# MCU_Peripherals.net
KiCad netlist of a schematic drawn in Altium Designer
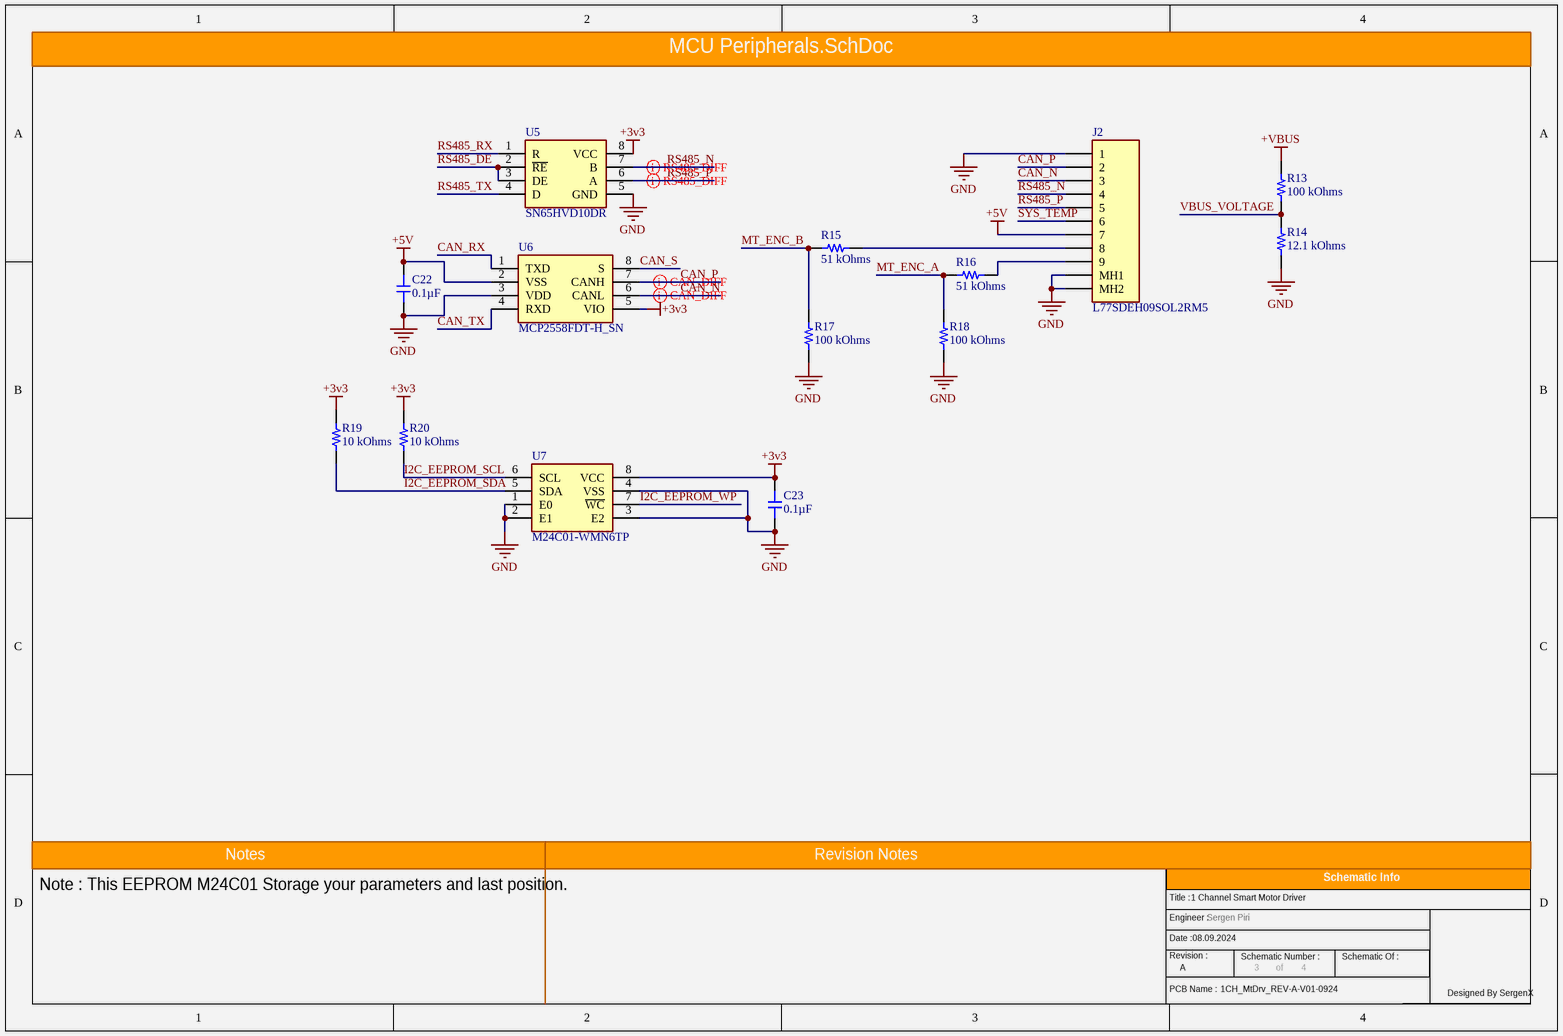
[diagram p0: MCU Peripherals.SchDoc]

(export (version "E")
  (design (tool "Eeschema 10.0.6"))
  (components
    (comp (ref "C22")
      (value "0.1µF")
      (footprint "0603_Footprint")
      (description "0.1uF 0603 Surface Capacitor")
      (libsource (lib "MainLibrary") (part "0.1uF 0603 Surface Capacitor"))
    )
    (comp (ref "C23")
      (value "0.1µF")
      (footprint "0603_Footprint")
      (description "0.1uF 0603 Surface Capacitor")
      (libsource (lib "MainLibrary") (part "0.1uF 0603 Surface Capacitor"))
    )
    (comp (ref "J2")
      (value "L77SDEH09SOL2RM5")
      (footprint "L77SDEH09SOL2RM5")
      (fields (field (name "MOUSER PART NUMBER") "523-L77SDEH09SOL2RM5"))
      (libsource (lib "MainLibrary") (part "L77SDEH09SOL2RM5"))
    )
    (comp (ref "R13")
      (value "100 kOhms")
      (footprint "0603_RES")
      (description "100k Ohm 0603")
      (libsource (lib "MainLibrary") (part "100k Ohm 0603"))
    )
    (comp (ref "R14")
      (value "12.1 kOhms")
      (footprint "0603_RES")
      (description "12.1 kOhms 0603")
      (libsource (lib "MainLibrary") (part "12.1 kOhms 0603"))
    )
    (comp (ref "R15")
      (value "51 kOhms")
      (footprint "0603_RES")
      (description "51k Ohm 0603")
      (libsource (lib "MainLibrary") (part "51k Ohm 0603"))
    )
    (comp (ref "R16")
      (value "51 kOhms")
      (footprint "0603_RES")
      (description "51k Ohm 0603")
      (libsource (lib "MainLibrary") (part "51k Ohm 0603"))
    )
    (comp (ref "R17")
      (value "100 kOhms")
      (footprint "0603_RES")
      (description "100k Ohm 0603")
      (libsource (lib "MainLibrary") (part "100k Ohm 0603"))
    )
    (comp (ref "R18")
      (value "100 kOhms")
      (footprint "0603_RES")
      (description "100k Ohm 0603")
      (libsource (lib "MainLibrary") (part "100k Ohm 0603"))
    )
    (comp (ref "R19")
      (value "10 kOhms")
      (footprint "0603_RES")
      (description "10 kOhms 0603")
      (libsource (lib "MainLibrary") (part "10 kOhms 0603"))
    )
    (comp (ref "R20")
      (value "10 kOhms")
      (footprint "0603_RES")
      (description "10 kOhms 0603")
      (libsource (lib "MainLibrary") (part "10 kOhms 0603"))
    )
    (comp (ref "U5")
      (value "SN65HVD10DR")
      (footprint "SOIC127P600X175-8N")
      (description "3.3V RS485 TRANSRECEIVER IC")
      (fields (field (name "MOUSER PART NUMBER") "595-SN65HVD10DR"))
      (libsource (lib "MainLibrary") (part "SN65HVD10DR"))
    )
    (comp (ref "U6")
      (value "MCP2558FDT-H_SN")
      (footprint "SOIC127P600X175-8N")
      (description "CAN Interface IC CAN FD Transceiver with Silent Mode")
      (fields
        (field (name "MANUFACTURER_PART_NUMBER") "MCP2558FDT-H/SN")
        (field (name "MOUSER PART NUMBER") "579-MCP2558FDT-H/SN")
      )
      (libsource (lib "MainLibrary") (part "MCP2558FDT-H_SN"))
    )
    (comp (ref "U7")
      (value "M24C01-WMN6TP")
      (footprint "MainLibrary:SOIC127P600X175-8N")
      (description "EEPROM Memory IC 1Kb (128 x 8) IÂ²C 400kHz 900ns 8-SO")
      (fields (field (name "MF") "STMicroelectronics"))
      (libsource (lib "MainLibrary") (part "M24C01-WMN6TP"))
    )
  )
  (nets
    (net (code "1") (name "+3v3") (class "Default")
      (node (ref "C23") (pin "1") (pinfunction "1_1") (pintype "passive"))
      (node (ref "R19") (pin "2") (pinfunction "2_2") (pintype "passive"))
      (node (ref "R20") (pin "2") (pinfunction "2_2") (pintype "passive"))
      (node (ref "U5") (pin "8") (pinfunction "VCC_8") (pintype "passive"))
      (node (ref "U6") (pin "5") (pinfunction "VIO_5") (pintype "passive"))
      (node (ref "U7") (pin "8") (pinfunction "VCC_8") (pintype "power_in"))
    )
    (net (code "2") (name "+5V") (class "Default")
      (node (ref "C22") (pin "1") (pinfunction "1_1") (pintype "passive"))
      (node (ref "J2") (pin "7") (pinfunction "7_7") (pintype "passive"))
      (node (ref "U6") (pin "2") (pinfunction "VSS_2") (pintype "passive"))
    )
    (net (code "3") (name "+VBUS") (class "Default")
      (node (ref "R13") (pin "2") (pinfunction "2_2") (pintype "passive"))
    )
    (net (code "4") (name "/CAN_N") (class "Default")
      (node (ref "J2") (pin "3") (pinfunction "3_3") (pintype "passive"))
      (node (ref "U6") (pin "6") (pinfunction "CANL_6") (pintype "passive"))
    )
    (net (code "5") (name "/CAN_P") (class "Default")
      (node (ref "J2") (pin "2") (pinfunction "2_2") (pintype "passive"))
      (node (ref "U6") (pin "7") (pinfunction "CANH_7") (pintype "passive"))
    )
    (net (code "6") (name "/CAN_RX") (class "Default")
      (node (ref "U6") (pin "1") (pinfunction "TXD_1") (pintype "passive"))
    )
    (net (code "7") (name "/CAN_S") (class "Default")
      (node (ref "U6") (pin "8") (pinfunction "S_8") (pintype "passive"))
    )
    (net (code "8") (name "/CAN_TX") (class "Default")
      (node (ref "U6") (pin "4") (pinfunction "RXD_4") (pintype "passive"))
    )
    (net (code "9") (name "/I2C_EEPROM_SCL") (class "Default")
      (node (ref "R20") (pin "1") (pinfunction "1_1") (pintype "passive"))
      (node (ref "U7") (pin "6") (pinfunction "SCL_6") (pintype "passive"))
    )
    (net (code "10") (name "/I2C_EEPROM_SDA") (class "Default")
      (node (ref "R19") (pin "1") (pinfunction "1_1") (pintype "passive"))
      (node (ref "U7") (pin "5") (pinfunction "SDA_5") (pintype "passive"))
    )
    (net (code "11") (name "/I2C_EEPROM_WP") (class "Default")
      (node (ref "U7") (pin "7") (pinfunction "~{WC}_7") (pintype "passive"))
    )
    (net (code "12") (name "/MT_ENC_A") (class "Default")
      (node (ref "R16") (pin "2") (pinfunction "2_2") (pintype "passive"))
      (node (ref "R18") (pin "2") (pinfunction "2_2") (pintype "passive"))
    )
    (net (code "13") (name "/MT_ENC_B") (class "Default")
      (node (ref "R15") (pin "2") (pinfunction "2_2") (pintype "passive"))
      (node (ref "R17") (pin "2") (pinfunction "2_2") (pintype "passive"))
    )
    (net (code "14") (name "/RS485_DE") (class "Default")
      (node (ref "U5") (pin "2") (pinfunction "~{RE}_2") (pintype "passive"))
      (node (ref "U5") (pin "3") (pinfunction "DE_3") (pintype "passive"))
    )
    (net (code "15") (name "/RS485_N") (class "Default")
      (node (ref "J2") (pin "4") (pinfunction "4_4") (pintype "passive"))
      (node (ref "U5") (pin "7") (pinfunction "B_7") (pintype "passive"))
    )
    (net (code "16") (name "/RS485_P") (class "Default")
      (node (ref "J2") (pin "5") (pinfunction "5_5") (pintype "passive"))
      (node (ref "U5") (pin "6") (pinfunction "A_6") (pintype "passive"))
    )
    (net (code "17") (name "/RS485_RX") (class "Default")
      (node (ref "U5") (pin "1") (pinfunction "R_1") (pintype "passive"))
    )
    (net (code "18") (name "/RS485_TX") (class "Default")
      (node (ref "U5") (pin "4") (pinfunction "D_4") (pintype "passive"))
    )
    (net (code "19") (name "/SYS_TEMP") (class "Default")
      (node (ref "J2") (pin "6") (pinfunction "6_6") (pintype "passive"))
    )
    (net (code "20") (name "/VBUS_VOLTAGE") (class "Default")
      (node (ref "R13") (pin "1") (pinfunction "1_1") (pintype "passive"))
      (node (ref "R14") (pin "2") (pinfunction "2_2") (pintype "passive"))
    )
    (net (code "21") (name "GND") (class "Default")
      (node (ref "C22") (pin "2") (pinfunction "2_2") (pintype "passive"))
      (node (ref "C23") (pin "2") (pinfunction "2_2") (pintype "passive"))
      (node (ref "J2") (pin "1") (pinfunction "1_1") (pintype "passive"))
      (node (ref "J2") (pin "MH1") (pinfunction "MH1_MH1") (pintype "passive"))
      (node (ref "J2") (pin "MH2") (pinfunction "MH2_MH2") (pintype "passive"))
      (node (ref "R14") (pin "1") (pinfunction "1_1") (pintype "passive"))
      (node (ref "R17") (pin "1") (pinfunction "1_1") (pintype "passive"))
      (node (ref "R18") (pin "1") (pinfunction "1_1") (pintype "passive"))
      (node (ref "U5") (pin "5") (pinfunction "GND_5") (pintype "passive"))
      (node (ref "U6") (pin "3") (pinfunction "VDD_3") (pintype "passive"))
      (node (ref "U7") (pin "1") (pinfunction "E0_1") (pintype "passive"))
      (node (ref "U7") (pin "2") (pinfunction "E1_2") (pintype "passive"))
      (node (ref "U7") (pin "3") (pinfunction "E2_3") (pintype "passive"))
      (node (ref "U7") (pin "4") (pinfunction "VSS_4") (pintype "passive"))
    )
    (net (code "22") (name "Net-(J2-Pad8)") (class "Default")
      (node (ref "J2") (pin "8") (pinfunction "8_8") (pintype "passive"))
      (node (ref "R15") (pin "1") (pinfunction "1_1") (pintype "passive"))
    )
    (net (code "23") (name "Net-(J2-Pad9)") (class "Default")
      (node (ref "J2") (pin "9") (pinfunction "9_9") (pintype "passive"))
      (node (ref "R16") (pin "1") (pinfunction "1_1") (pintype "passive"))
    )
  )
)
